# Connectors.net
KiCad netlist of a schematic drawn in Altium Designer
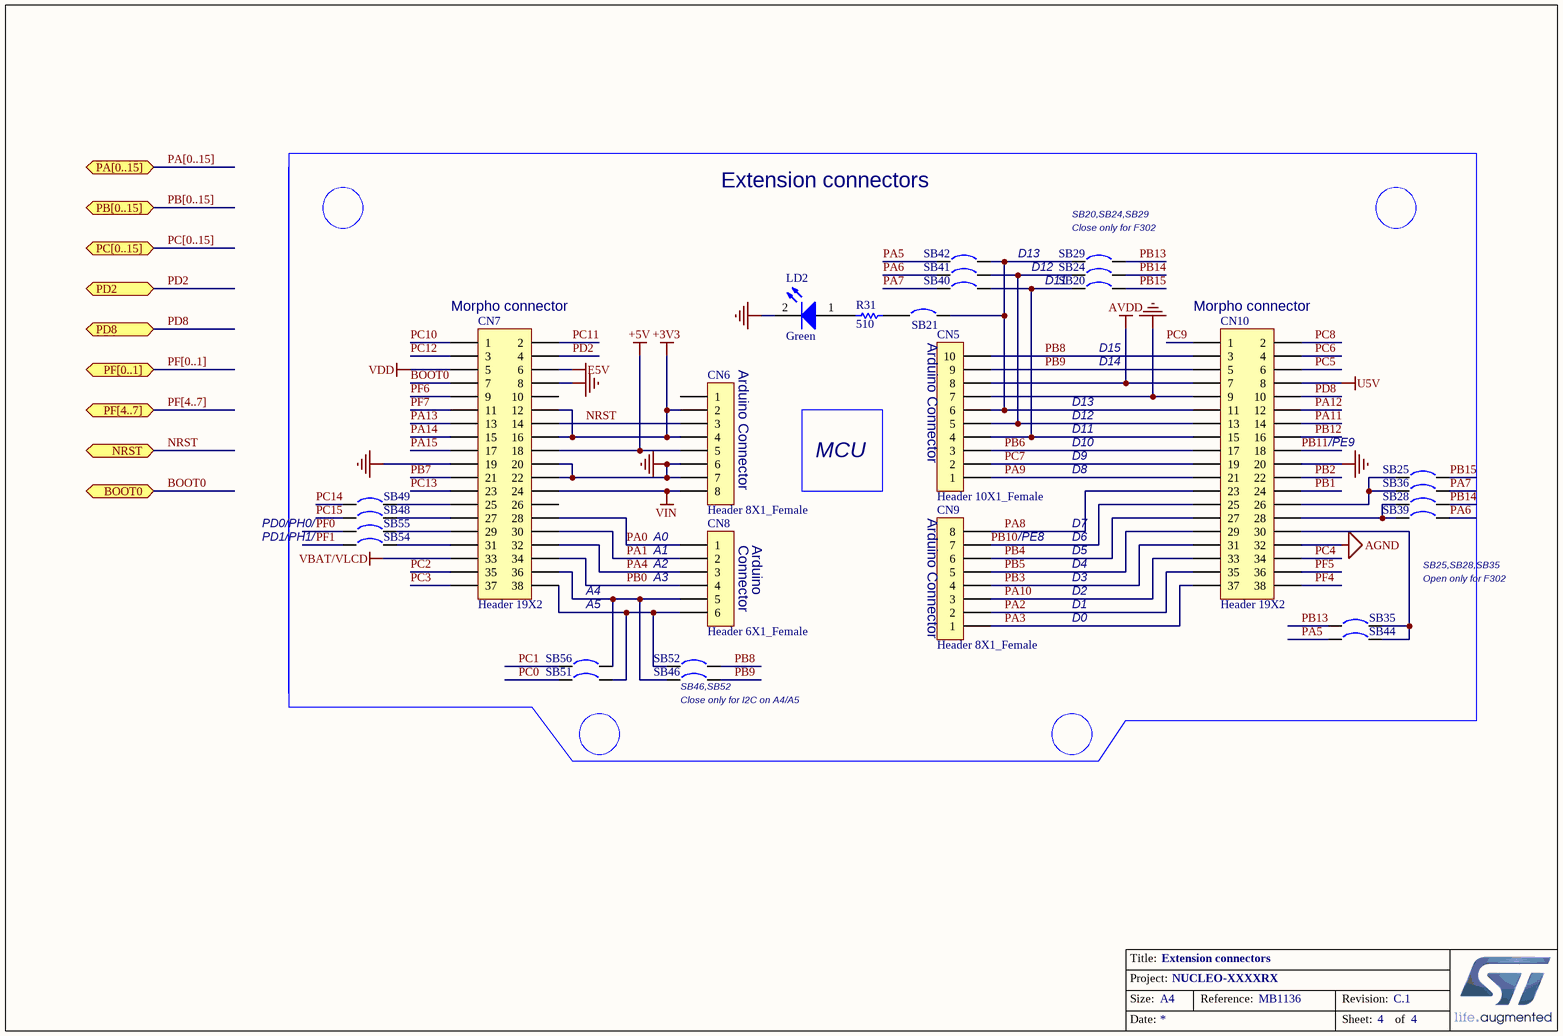
[diagram p0: Connectors.SchDoc]

(export (version "E")
  (design (tool "Eeschema 10.0.6"))
  (components
    (comp (ref "CN5")
      (value "Header 10X1_Female")
      (footprint "1*10P_FEMALE")
      (description "Header, 10-Pin, Single row,female")
      (fields (field (name "PUBLISHER") "Altium Limited"))
      (libsource (lib "Nucleo_64") (part "Header 10X1_Female"))
    )
    (comp (ref "CN6")
      (value "Header 8X1_Female")
      (footprint "1*8P_FEMALE")
      (description "Header, 8-Pin, Single row,female")
      (fields (field (name "PUBLISHER") "Altium Limited"))
      (libsource (lib "Nucleo_64") (part "Header 8X1_Female"))
    )
    (comp (ref "CN7")
      (value "Header 19X2")
      (footprint "2*19P")
      (description "Header, 19-Pin, Dual row")
      (fields (field (name "PUBLISHER") "Altium Limited"))
      (libsource (lib "Nucleo_64_1") (part "Header 19X2"))
    )
    (comp (ref "CN8")
      (value "Header 6X1_Female")
      (footprint "1*6P_FEMALE")
      (description "Header, 6-Pin, Single row,female")
      (fields (field (name "PUBLISHER") "Altium Limited"))
      (libsource (lib "Nucleo_64") (part "Header 6X1_Female"))
    )
    (comp (ref "CN9")
      (value "Header 8X1_Female")
      (footprint "1*8P_FEMALE")
      (description "Header, 8-Pin, Single row,female")
      (fields (field (name "PUBLISHER") "Altium Limited"))
      (libsource (lib "") (part "Header 8X1_Female_1"))
    )
    (comp (ref "CN10")
      (value "Header 19X2")
      (footprint "2*19P")
      (description "Header, 19-Pin, Dual row")
      (fields (field (name "PUBLISHER") "Altium Limited"))
      (libsource (lib "Nucleo_64_1") (part "Header 19X2"))
    )
    (comp (ref "LD2")
      (value "Green")
      (footprint "0603D")
      (description "Typical RED, GREEN, YELLOW, AMBER GaAs LED")
      (fields (field (name "PUBLISHER") "Altium Limited"))
      (libsource (lib "Miscellaneous Devices") (part "LED2"))
    )
    (comp (ref "R31")
      (value "510")
      (footprint "0603R")
      (description "Resistor")
      (fields (field (name "PUBLISHER") "Altium Limited"))
      (libsource (lib "Miscellaneous Devices") (part "Res1"))
    )
    (comp (ref "SB20")
      (value "Circuit Breaker")
      (footprint "JP2_SMD")
      (fields (field (name "PUBLISHER") "Altium Limited"))
      (libsource (lib "MCD_TOOLS") (part "Circuit Breaker"))
    )
    (comp (ref "SB21")
      (value "Circuit Breaker")
      (footprint "JP2_SMD")
      (fields (field (name "PUBLISHER") "Altium Limited"))
      (libsource (lib "MCD_TOOLS") (part "Circuit Breaker"))
    )
    (comp (ref "SB24")
      (value "Circuit Breaker")
      (footprint "JP2_SMD")
      (fields (field (name "PUBLISHER") "Altium Limited"))
      (libsource (lib "MCD_TOOLS") (part "Circuit Breaker"))
    )
    (comp (ref "SB25")
      (value "Circuit Breaker")
      (footprint "JP2_SMD")
      (fields (field (name "PUBLISHER") "Altium Limited"))
      (libsource (lib "") (part "Circuit Breaker_1"))
    )
    (comp (ref "SB28")
      (value "Circuit Breaker")
      (footprint "JP2_SMD")
      (fields (field (name "PUBLISHER") "Altium Limited"))
      (libsource (lib "") (part "Circuit Breaker_1"))
    )
    (comp (ref "SB29")
      (value "Circuit Breaker")
      (footprint "JP2_SMD")
      (fields (field (name "PUBLISHER") "Altium Limited"))
      (libsource (lib "MCD_TOOLS") (part "Circuit Breaker"))
    )
    (comp (ref "SB35")
      (value "Circuit Breaker")
      (footprint "JP2_SMD")
      (fields (field (name "PUBLISHER") "Altium Limited"))
      (libsource (lib "") (part "Circuit Breaker_1"))
    )
    (comp (ref "SB36")
      (value "Circuit Breaker")
      (footprint "JP2_SMD")
      (fields (field (name "PUBLISHER") "Altium Limited"))
      (libsource (lib "") (part "Circuit Breaker_1"))
    )
    (comp (ref "SB39")
      (value "Circuit Breaker")
      (footprint "JP2_SMD")
      (fields (field (name "PUBLISHER") "Altium Limited"))
      (libsource (lib "") (part "Circuit Breaker_1"))
    )
    (comp (ref "SB40")
      (value "Circuit Breaker")
      (footprint "JP2_SMD")
      (fields (field (name "PUBLISHER") "Altium Limited"))
      (libsource (lib "MCD_TOOLS") (part "Circuit Breaker"))
    )
    (comp (ref "SB41")
      (value "Circuit Breaker")
      (footprint "JP2_SMD")
      (fields (field (name "PUBLISHER") "Altium Limited"))
      (libsource (lib "MCD_TOOLS") (part "Circuit Breaker"))
    )
    (comp (ref "SB42")
      (value "Circuit Breaker")
      (footprint "JP2_SMD")
      (fields (field (name "PUBLISHER") "Altium Limited"))
      (libsource (lib "MCD_TOOLS") (part "Circuit Breaker"))
    )
    (comp (ref "SB44")
      (value "Circuit Breaker")
      (footprint "JP2_SMD")
      (fields (field (name "PUBLISHER") "Altium Limited"))
      (libsource (lib "") (part "Circuit Breaker_1"))
    )
    (comp (ref "SB46")
      (value "Circuit Breaker")
      (footprint "JP2_SMD")
      (fields (field (name "PUBLISHER") "Altium Limited"))
      (libsource (lib "MCD_TOOLS") (part "Circuit Breaker"))
    )
    (comp (ref "SB48")
      (value "Circuit Breaker")
      (footprint "JP2_SMD")
      (fields (field (name "PUBLISHER") "Altium Limited"))
      (libsource (lib "") (part "Circuit Breaker_1"))
    )
    (comp (ref "SB49")
      (value "Circuit Breaker")
      (footprint "JP2_SMD")
      (fields (field (name "PUBLISHER") "Altium Limited"))
      (libsource (lib "") (part "Circuit Breaker_1"))
    )
    (comp (ref "SB51")
      (value "Circuit Breaker")
      (footprint "JP2_SMD")
      (fields (field (name "PUBLISHER") "Altium Limited"))
      (libsource (lib "MCD_TOOLS") (part "Circuit Breaker"))
    )
    (comp (ref "SB52")
      (value "Circuit Breaker")
      (footprint "JP2_SMD")
      (fields (field (name "PUBLISHER") "Altium Limited"))
      (libsource (lib "MCD_TOOLS") (part "Circuit Breaker"))
    )
    (comp (ref "SB54")
      (value "Circuit Breaker")
      (footprint "JP2_SMD")
      (fields (field (name "PUBLISHER") "Altium Limited"))
      (libsource (lib "") (part "Circuit Breaker_1"))
    )
    (comp (ref "SB55")
      (value "Circuit Breaker")
      (footprint "JP2_SMD")
      (fields (field (name "PUBLISHER") "Altium Limited"))
      (libsource (lib "") (part "Circuit Breaker_1"))
    )
    (comp (ref "SB56")
      (value "Circuit Breaker")
      (footprint "JP2_SMD")
      (fields (field (name "PUBLISHER") "Altium Limited"))
      (libsource (lib "MCD_TOOLS") (part "Circuit Breaker"))
    )
  )
  (nets
    (net (code "1") (name "+3V3") (class "Default")
      (node (ref "CN6") (pin "2") (pinfunction "2_2") (pintype "passive"))
      (node (ref "CN6") (pin "4") (pinfunction "4_4") (pintype "passive"))
      (node (ref "CN7") (pin "12") (pinfunction "12_12") (pintype "passive"))
      (node (ref "CN7") (pin "16") (pinfunction "16_16") (pintype "passive"))
    )
    (net (code "2") (name "+5V") (class "Default")
      (node (ref "CN6") (pin "5") (pinfunction "5_5") (pintype "passive"))
      (node (ref "CN7") (pin "18") (pinfunction "18_18") (pintype "passive"))
    )
    (net (code "3") (name "/BOOT0") (class "Default")
      (node (ref "CN7") (pin "7") (pinfunction "7_7") (pintype "passive"))
    )
    (net (code "4") (name "/NRST") (class "Default")
      (node (ref "CN6") (pin "3") (pinfunction "3_3") (pintype "passive"))
      (node (ref "CN7") (pin "14") (pinfunction "14_14") (pintype "passive"))
    )
    (net (code "5") (name "/PA0") (class "Default")
      (node (ref "CN7") (pin "28") (pinfunction "28_28") (pintype "passive"))
      (node (ref "CN8") (pin "1") (pinfunction "1_1") (pintype "passive"))
    )
    (net (code "6") (name "/PA1") (class "Default")
      (node (ref "CN7") (pin "30") (pinfunction "30_30") (pintype "passive"))
      (node (ref "CN8") (pin "2") (pinfunction "2_2") (pintype "passive"))
    )
    (net (code "7") (name "/PA2") (class "Default")
      (node (ref "CN10") (pin "35") (pinfunction "35_35") (pintype "passive"))
      (node (ref "CN9") (pin "2") (pinfunction "2_2") (pintype "passive"))
    )
    (net (code "8") (name "/PA3") (class "Default")
      (node (ref "CN10") (pin "37") (pinfunction "37_37") (pintype "passive"))
      (node (ref "CN9") (pin "1") (pinfunction "1_1") (pintype "passive"))
    )
    (net (code "9") (name "/PA4") (class "Default")
      (node (ref "CN7") (pin "32") (pinfunction "32_32") (pintype "passive"))
      (node (ref "CN8") (pin "3") (pinfunction "3_3") (pintype "passive"))
    )
    (net (code "10") (name "/PA5") (class "Default")
      (node (ref "SB42") (pin "1") (pinfunction "1_1") (pintype "passive"))
      (node (ref "SB44") (pin "2") (pinfunction "2_2") (pintype "passive"))
    )
    (net (code "11") (name "/PA6") (class "Default")
      (node (ref "SB39") (pin "1") (pinfunction "1_1") (pintype "passive"))
      (node (ref "SB41") (pin "1") (pinfunction "1_1") (pintype "passive"))
    )
    (net (code "12") (name "/PA7") (class "Default")
      (node (ref "SB36") (pin "1") (pinfunction "1_1") (pintype "passive"))
      (node (ref "SB40") (pin "1") (pinfunction "1_1") (pintype "passive"))
    )
    (net (code "13") (name "/PA8") (class "Default")
      (node (ref "CN10") (pin "23") (pinfunction "23_23") (pintype "passive"))
      (node (ref "CN9") (pin "8") (pinfunction "8_8") (pintype "passive"))
    )
    (net (code "14") (name "/PA9") (class "Default")
      (node (ref "CN10") (pin "21") (pinfunction "21_21") (pintype "passive"))
      (node (ref "CN5") (pin "1") (pinfunction "1_1") (pintype "passive"))
    )
    (net (code "15") (name "/PA10") (class "Default")
      (node (ref "CN10") (pin "33") (pinfunction "33_33") (pintype "passive"))
      (node (ref "CN9") (pin "3") (pinfunction "3_3") (pintype "passive"))
    )
    (net (code "16") (name "/PA11") (class "Default")
      (node (ref "CN10") (pin "14") (pinfunction "14_14") (pintype "passive"))
    )
    (net (code "17") (name "/PA12") (class "Default")
      (node (ref "CN10") (pin "12") (pinfunction "12_12") (pintype "passive"))
    )
    (net (code "18") (name "/PA13") (class "Default")
      (node (ref "CN7") (pin "13") (pinfunction "13_13") (pintype "passive"))
    )
    (net (code "19") (name "/PA14") (class "Default")
      (node (ref "CN7") (pin "15") (pinfunction "15_15") (pintype "passive"))
    )
    (net (code "20") (name "/PA15") (class "Default")
      (node (ref "CN7") (pin "17") (pinfunction "17_17") (pintype "passive"))
    )
    (net (code "22") (name "/PB0") (class "Default")
      (node (ref "CN7") (pin "34") (pinfunction "34_34") (pintype "passive"))
      (node (ref "CN8") (pin "4") (pinfunction "4_4") (pintype "passive"))
    )
    (net (code "23") (name "/PB1") (class "Default")
      (node (ref "CN10") (pin "24") (pinfunction "24_24") (pintype "passive"))
    )
    (net (code "24") (name "/PB2") (class "Default")
      (node (ref "CN10") (pin "22") (pinfunction "22_22") (pintype "passive"))
    )
    (net (code "25") (name "/PB3") (class "Default")
      (node (ref "CN10") (pin "31") (pinfunction "31_31") (pintype "passive"))
      (node (ref "CN9") (pin "4") (pinfunction "4_4") (pintype "passive"))
    )
    (net (code "26") (name "/PB4") (class "Default")
      (node (ref "CN10") (pin "27") (pinfunction "27_27") (pintype "passive"))
      (node (ref "CN9") (pin "6") (pinfunction "6_6") (pintype "passive"))
    )
    (net (code "27") (name "/PB5") (class "Default")
      (node (ref "CN10") (pin "29") (pinfunction "29_29") (pintype "passive"))
      (node (ref "CN9") (pin "5") (pinfunction "5_5") (pintype "passive"))
    )
    (net (code "28") (name "/PB6") (class "Default")
      (node (ref "CN10") (pin "17") (pinfunction "17_17") (pintype "passive"))
      (node (ref "CN5") (pin "3") (pinfunction "3_3") (pintype "passive"))
    )
    (net (code "29") (name "/PB7") (class "Default")
      (node (ref "CN7") (pin "21") (pinfunction "21_21") (pintype "passive"))
    )
    (net (code "30") (name "/PB8") (class "Default")
      (node (ref "CN10") (pin "3") (pinfunction "3_3") (pintype "passive"))
      (node (ref "CN5") (pin "10") (pinfunction "10_10") (pintype "passive"))
      (node (ref "SB52") (pin "2") (pinfunction "2_2") (pintype "passive"))
    )
    (net (code "31") (name "/PB9") (class "Default")
      (node (ref "CN10") (pin "5") (pinfunction "5_5") (pintype "passive"))
      (node (ref "CN5") (pin "9") (pinfunction "9_9") (pintype "passive"))
      (node (ref "SB46") (pin "2") (pinfunction "2_2") (pintype "passive"))
    )
    (net (code "32") (name "/PB10") (class "Default")
      (node (ref "CN10") (pin "25") (pinfunction "25_25") (pintype "passive"))
      (node (ref "CN9") (pin "7") (pinfunction "7_7") (pintype "passive"))
    )
    (net (code "33") (name "/PB11") (class "Default")
      (node (ref "CN10") (pin "18") (pinfunction "18_18") (pintype "passive"))
    )
    (net (code "34") (name "/PB12") (class "Default")
      (node (ref "CN10") (pin "16") (pinfunction "16_16") (pintype "passive"))
    )
    (net (code "35") (name "/PB13") (class "Default")
      (node (ref "SB29") (pin "2") (pinfunction "2_2") (pintype "passive"))
      (node (ref "SB35") (pin "2") (pinfunction "2_2") (pintype "passive"))
    )
    (net (code "36") (name "/PB14") (class "Default")
      (node (ref "SB24") (pin "2") (pinfunction "2_2") (pintype "passive"))
      (node (ref "SB28") (pin "1") (pinfunction "1_1") (pintype "passive"))
    )
    (net (code "37") (name "/PB15") (class "Default")
      (node (ref "SB20") (pin "2") (pinfunction "2_2") (pintype "passive"))
      (node (ref "SB25") (pin "1") (pinfunction "1_1") (pintype "passive"))
    )
    (net (code "39") (name "/PC0") (class "Default")
      (node (ref "SB51") (pin "1") (pinfunction "1_1") (pintype "passive"))
    )
    (net (code "40") (name "/PC1") (class "Default")
      (node (ref "SB56") (pin "1") (pinfunction "1_1") (pintype "passive"))
    )
    (net (code "41") (name "/PC2") (class "Default")
      (node (ref "CN7") (pin "35") (pinfunction "35_35") (pintype "passive"))
    )
    (net (code "42") (name "/PC3") (class "Default")
      (node (ref "CN7") (pin "37") (pinfunction "37_37") (pintype "passive"))
    )
    (net (code "43") (name "/PC4") (class "Default")
      (node (ref "CN10") (pin "34") (pinfunction "34_34") (pintype "passive"))
    )
    (net (code "44") (name "/PC5") (class "Default")
      (node (ref "CN10") (pin "6") (pinfunction "6_6") (pintype "passive"))
    )
    (net (code "45") (name "/PC6") (class "Default")
      (node (ref "CN10") (pin "4") (pinfunction "4_4") (pintype "passive"))
    )
    (net (code "46") (name "/PC7") (class "Default")
      (node (ref "CN10") (pin "19") (pinfunction "19_19") (pintype "passive"))
      (node (ref "CN5") (pin "2") (pinfunction "2_2") (pintype "passive"))
    )
    (net (code "47") (name "/PC8") (class "Default")
      (node (ref "CN10") (pin "2") (pinfunction "2_2") (pintype "passive"))
    )
    (net (code "48") (name "/PC9") (class "Default")
      (node (ref "CN10") (pin "1") (pinfunction "1_1") (pintype "passive"))
    )
    (net (code "49") (name "/PC10") (class "Default")
      (node (ref "CN7") (pin "1") (pinfunction "1_1") (pintype "passive"))
    )
    (net (code "50") (name "/PC11") (class "Default")
      (node (ref "CN7") (pin "2") (pinfunction "2_2") (pintype "passive"))
    )
    (net (code "51") (name "/PC12") (class "Default")
      (node (ref "CN7") (pin "3") (pinfunction "3_3") (pintype "passive"))
    )
    (net (code "52") (name "/PC13") (class "Default")
      (node (ref "CN7") (pin "23") (pinfunction "23_23") (pintype "passive"))
    )
    (net (code "53") (name "/PC14") (class "Default")
      (node (ref "SB49") (pin "2") (pinfunction "2_2") (pintype "passive"))
    )
    (net (code "54") (name "/PC15") (class "Default")
      (node (ref "SB48") (pin "2") (pinfunction "2_2") (pintype "passive"))
    )
    (net (code "56") (name "/PD2") (class "Default")
      (node (ref "CN7") (pin "4") (pinfunction "4_4") (pintype "passive"))
    )
    (net (code "57") (name "/PD8") (class "Default")
      (node (ref "CN10") (pin "10") (pinfunction "10_10") (pintype "passive"))
    )
    (net (code "58") (name "/PF0") (class "Default")
      (node (ref "SB55") (pin "2") (pinfunction "2_2") (pintype "passive"))
    )
    (net (code "59") (name "/PF1") (class "Default")
      (node (ref "SB54") (pin "2") (pinfunction "2_2") (pintype "passive"))
    )
    (net (code "60") (name "/PF4") (class "Default")
      (node (ref "CN10") (pin "38") (pinfunction "38_38") (pintype "passive"))
    )
    (net (code "61") (name "/PF5") (class "Default")
      (node (ref "CN10") (pin "36") (pinfunction "36_36") (pintype "passive"))
    )
    (net (code "62") (name "/PF6") (class "Default")
      (node (ref "CN7") (pin "9") (pinfunction "9_9") (pintype "passive"))
    )
    (net (code "63") (name "/PF7") (class "Default")
      (node (ref "CN7") (pin "11") (pinfunction "11_11") (pintype "passive"))
    )
    (net (code "66") (name "AGND") (class "Default")
      (node (ref "CN10") (pin "32") (pinfunction "32_32") (pintype "passive"))
    )
    (net (code "67") (name "AVDD") (class "Default")
      (node (ref "CN10") (pin "7") (pinfunction "7_7") (pintype "passive"))
      (node (ref "CN5") (pin "8") (pinfunction "8_8") (pintype "passive"))
    )
    (net (code "68") (name "E5V") (class "Default")
      (node (ref "CN7") (pin "6") (pinfunction "6_6") (pintype "passive"))
    )
    (net (code "69") (name "GND") (class "Default")
      (node (ref "CN10") (pin "20") (pinfunction "20_20") (pintype "passive"))
      (node (ref "CN10") (pin "9") (pinfunction "9_9") (pintype "passive"))
      (node (ref "CN5") (pin "7") (pinfunction "7_7") (pintype "passive"))
      (node (ref "CN6") (pin "6") (pinfunction "6_6") (pintype "passive"))
      (node (ref "CN6") (pin "7") (pinfunction "7_7") (pintype "passive"))
      (node (ref "CN7") (pin "19") (pinfunction "19_19") (pintype "passive"))
      (node (ref "CN7") (pin "20") (pinfunction "20_20") (pintype "passive"))
      (node (ref "CN7") (pin "22") (pinfunction "22_22") (pintype "passive"))
      (node (ref "CN7") (pin "8") (pinfunction "8_8") (pintype "passive"))
      (node (ref "LD2") (pin "2") (pinfunction "K_2") (pintype "passive"))
    )
    (net (code "70") (name "Net-(CN7-Pad25)") (class "Default")
      (node (ref "CN7") (pin "25") (pinfunction "25_25") (pintype "passive"))
      (node (ref "SB49") (pin "1") (pinfunction "1_1") (pintype "passive"))
    )
    (net (code "71") (name "Net-(CN7-Pad27)") (class "Default")
      (node (ref "CN7") (pin "27") (pinfunction "27_27") (pintype "passive"))
      (node (ref "SB48") (pin "1") (pinfunction "1_1") (pintype "passive"))
    )
    (net (code "72") (name "Net-(CN7-Pad29)") (class "Default")
      (node (ref "CN7") (pin "29") (pinfunction "29_29") (pintype "passive"))
      (node (ref "SB55") (pin "1") (pinfunction "1_1") (pintype "passive"))
    )
    (net (code "73") (name "Net-(CN7-Pad31)") (class "Default")
      (node (ref "CN7") (pin "31") (pinfunction "31_31") (pintype "passive"))
      (node (ref "SB54") (pin "1") (pinfunction "1_1") (pintype "passive"))
    )
    (net (code "74") (name "Net-(CN7-Pad36)") (class "Default")
      (node (ref "CN7") (pin "36") (pinfunction "36_36") (pintype "passive"))
      (node (ref "CN8") (pin "5") (pinfunction "5_5") (pintype "passive"))
      (node (ref "SB46") (pin "1") (pinfunction "1_1") (pintype "passive"))
      (node (ref "SB56") (pin "2") (pinfunction "2_2") (pintype "passive"))
    )
    (net (code "75") (name "Net-(CN7-Pad38)") (class "Default")
      (node (ref "CN7") (pin "38") (pinfunction "38_38") (pintype "passive"))
      (node (ref "CN8") (pin "6") (pinfunction "6_6") (pintype "passive"))
      (node (ref "SB51") (pin "2") (pinfunction "2_2") (pintype "passive"))
      (node (ref "SB52") (pin "1") (pinfunction "1_1") (pintype "passive"))
    )
    (net (code "76") (name "Net-(CN10-Pad11)") (class "Default")
      (node (ref "CN10") (pin "11") (pinfunction "11_11") (pintype "passive"))
      (node (ref "CN5") (pin "6") (pinfunction "6_6") (pintype "passive"))
      (node (ref "SB21") (pin "2") (pinfunction "2_2") (pintype "passive"))
      (node (ref "SB29") (pin "1") (pinfunction "1_1") (pintype "passive"))
      (node (ref "SB42") (pin "2") (pinfunction "2_2") (pintype "passive"))
    )
    (net (code "77") (name "Net-(CN10-Pad13)") (class "Default")
      (node (ref "CN10") (pin "13") (pinfunction "13_13") (pintype "passive"))
      (node (ref "CN5") (pin "5") (pinfunction "5_5") (pintype "passive"))
      (node (ref "SB24") (pin "1") (pinfunction "1_1") (pintype "passive"))
      (node (ref "SB41") (pin "2") (pinfunction "2_2") (pintype "passive"))
    )
    (net (code "78") (name "Net-(CN10-Pad15)") (class "Default")
      (node (ref "CN10") (pin "15") (pinfunction "15_15") (pintype "passive"))
      (node (ref "CN5") (pin "4") (pinfunction "4_4") (pintype "passive"))
      (node (ref "SB20") (pin "1") (pinfunction "1_1") (pintype "passive"))
      (node (ref "SB40") (pin "2") (pinfunction "2_2") (pintype "passive"))
    )
    (net (code "79") (name "Net-(CN10-Pad26)") (class "Default")
      (node (ref "CN10") (pin "26") (pinfunction "26_26") (pintype "passive"))
      (node (ref "SB25") (pin "2") (pinfunction "2_2") (pintype "passive"))
      (node (ref "SB36") (pin "2") (pinfunction "2_2") (pintype "passive"))
    )
    (net (code "80") (name "Net-(CN10-Pad28)") (class "Default")
      (node (ref "CN10") (pin "28") (pinfunction "28_28") (pintype "passive"))
      (node (ref "SB28") (pin "2") (pinfunction "2_2") (pintype "passive"))
      (node (ref "SB39") (pin "2") (pinfunction "2_2") (pintype "passive"))
    )
    (net (code "81") (name "Net-(CN10-Pad30)") (class "Default")
      (node (ref "CN10") (pin "30") (pinfunction "30_30") (pintype "passive"))
      (node (ref "SB35") (pin "1") (pinfunction "1_1") (pintype "passive"))
      (node (ref "SB44") (pin "1") (pinfunction "1_1") (pintype "passive"))
    )
    (net (code "82") (name "Net-(LD2-A)") (class "Default")
      (node (ref "LD2") (pin "1") (pinfunction "A_1") (pintype "passive"))
      (node (ref "R31") (pin "2") (pinfunction "2_2") (pintype "passive"))
    )
    (net (code "83") (name "Net-(R31-Pad1)") (class "Default")
      (node (ref "R31") (pin "1") (pinfunction "1_1") (pintype "passive"))
      (node (ref "SB21") (pin "1") (pinfunction "1_1") (pintype "passive"))
    )
    (net (code "84") (name "U5V") (class "Default")
      (node (ref "CN10") (pin "8") (pinfunction "8_8") (pintype "passive"))
    )
    (net (code "85") (name "VBAT{slash}VLCD") (class "Default")
      (node (ref "CN7") (pin "33") (pinfunction "33_33") (pintype "passive"))
    )
    (net (code "86") (name "VDD") (class "Default")
      (node (ref "CN7") (pin "5") (pinfunction "5_5") (pintype "passive"))
    )
    (net (code "87") (name "VIN") (class "Default")
      (node (ref "CN6") (pin "8") (pinfunction "8_8") (pintype "passive"))
      (node (ref "CN7") (pin "24") (pinfunction "24_24") (pintype "passive"))
    )
    (net (code "88") (name "unconnected-(CN6-Pad1)") (class "Default")
      (node (ref "CN6") (pin "1") (pinfunction "1_1") (pintype "passive"))
    )
    (net (code "89") (name "unconnected-(CN7-Pad10)") (class "Default")
      (node (ref "CN7") (pin "10") (pinfunction "10_10") (pintype "passive"))
    )
    (net (code "90") (name "unconnected-(CN7-Pad26)") (class "Default")
      (node (ref "CN7") (pin "26") (pinfunction "26_26") (pintype "passive"))
    )
  )
)
